# MUTE-basic.net
KiCad netlist of a schematic drawn in EAGLE
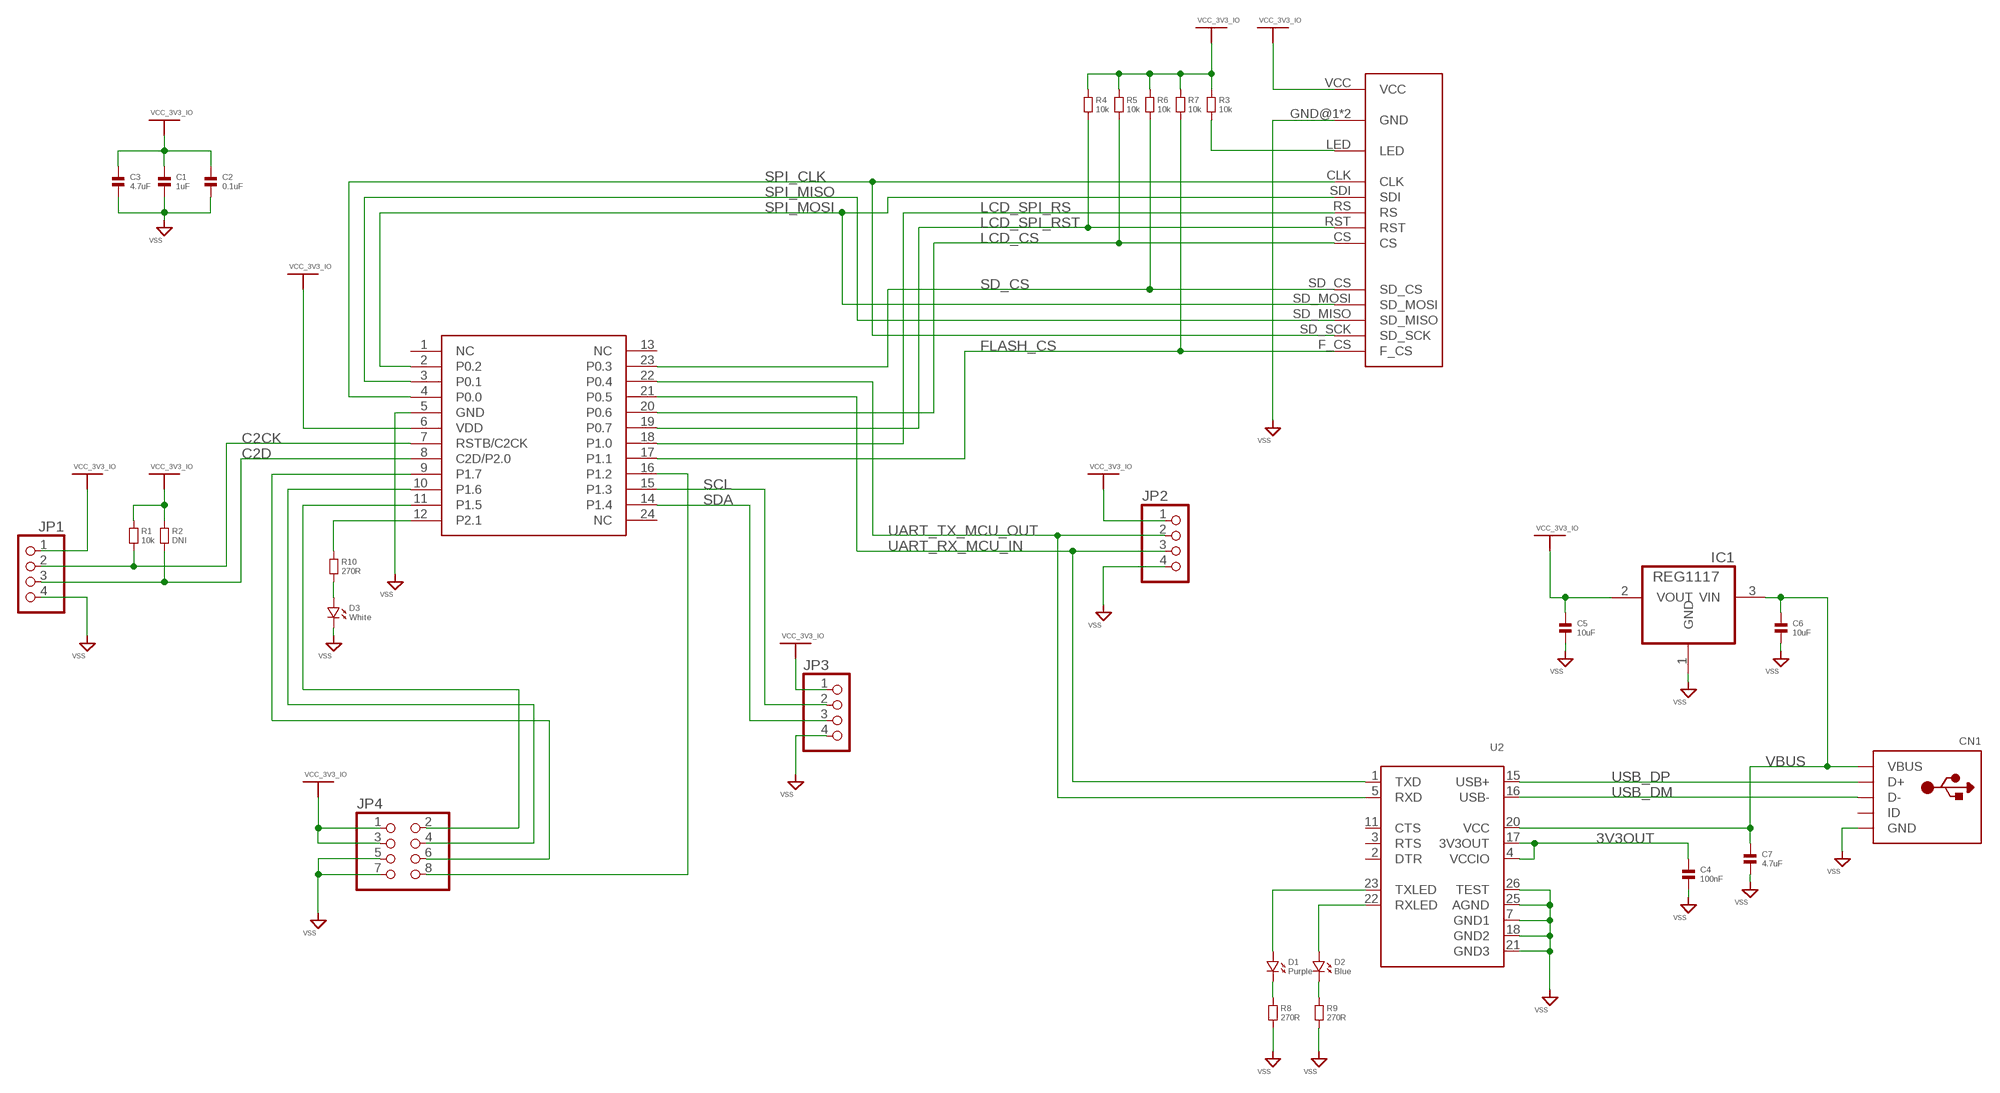
[diagram p0: schematic, sheet 1]

(export (version "E")
  (design (tool "Eeschema 10.0.6"))
  (components
    (comp (ref "C1")
      (value "1uF")
      (footprint "eagle-import:0603")
      (libsource (lib "eagle-import") (part "CAPACITOR.0603"))
    )
    (comp (ref "C2")
      (value "0.1uF")
      (footprint "eagle-import:0603")
      (libsource (lib "eagle-import") (part "CAPACITOR.0603"))
    )
    (comp (ref "C3")
      (value "4.7uF")
      (footprint "eagle-import:0603")
      (libsource (lib "eagle-import") (part "CAPACITOR.0603"))
    )
    (comp (ref "C4")
      (value "100nF")
      (footprint "eagle-import:0603")
      (libsource (lib "eagle-import") (part "CAPACITOR.0603"))
    )
    (comp (ref "C5")
      (value "10uF")
      (footprint "eagle-import:0603")
      (libsource (lib "eagle-import") (part "CAPACITOR.0603"))
    )
    (comp (ref "C6")
      (value "10uF")
      (footprint "eagle-import:0603")
      (libsource (lib "eagle-import") (part "CAPACITOR.0603"))
    )
    (comp (ref "C7")
      (value "4.7uF")
      (footprint "eagle-import:0603")
      (libsource (lib "eagle-import") (part "CAPACITOR.0603"))
    )
    (comp (ref "CN1")
      (value "USBMINIB")
      (footprint "eagle-import:USB-MINIB")
      (libsource (lib "eagle-import") (part "USBMINIB"))
    )
    (comp (ref "D1")
      (value "Purple")
      (footprint "eagle-import:0603.LED")
      (libsource (lib "eagle-import") (part "LED.0603"))
    )
    (comp (ref "D2")
      (value "Blue")
      (footprint "eagle-import:0603.LED")
      (libsource (lib "eagle-import") (part "LED.0603"))
    )
    (comp (ref "D3")
      (value "White")
      (footprint "eagle-import:0603.LED")
      (libsource (lib "eagle-import") (part "LED.0603"))
    )
    (comp (ref "IC1")
      (value "REG1117")
      (footprint "eagle-import:SOT223")
      (libsource (lib "eagle-import") (part "REG1117"))
    )
    (comp (ref "JP1")
      (value "PINHD-1X4")
      (footprint "eagle-import:1X04")
      (libsource (lib "eagle-import") (part "PINHD-1X4"))
    )
    (comp (ref "JP2")
      (value "PINHD-1X4")
      (footprint "eagle-import:1X04")
      (libsource (lib "eagle-import") (part "PINHD-1X4"))
    )
    (comp (ref "JP3")
      (value "PINHD-1X4")
      (footprint "eagle-import:1X04")
      (libsource (lib "eagle-import") (part "PINHD-1X4"))
    )
    (comp (ref "JP4")
      (value "PINHD-2X4")
      (footprint "eagle-import:2X04")
      (libsource (lib "eagle-import") (part "PINHD-2X4"))
    )
    (comp (ref "R1")
      (value "10k")
      (footprint "eagle-import:0603")
      (libsource (lib "eagle-import") (part "RESISTOR.0603"))
    )
    (comp (ref "R2")
      (value "DNI")
      (footprint "eagle-import:0603")
      (libsource (lib "eagle-import") (part "RESISTOR.0603"))
    )
    (comp (ref "R3")
      (value "10k")
      (footprint "eagle-import:0603")
      (libsource (lib "eagle-import") (part "RESISTOR.0603"))
    )
    (comp (ref "R4")
      (value "10k")
      (footprint "eagle-import:0603")
      (libsource (lib "eagle-import") (part "RESISTOR.0603"))
    )
    (comp (ref "R5")
      (value "10k")
      (footprint "eagle-import:0603")
      (libsource (lib "eagle-import") (part "RESISTOR.0603"))
    )
    (comp (ref "R6")
      (value "10k")
      (footprint "eagle-import:0603")
      (libsource (lib "eagle-import") (part "RESISTOR.0603"))
    )
    (comp (ref "R7")
      (value "10k")
      (footprint "eagle-import:0603")
      (libsource (lib "eagle-import") (part "RESISTOR.0603"))
    )
    (comp (ref "R8")
      (value "270R")
      (footprint "eagle-import:0603")
      (libsource (lib "eagle-import") (part "RESISTOR.0603"))
    )
    (comp (ref "R9")
      (value "270R")
      (footprint "eagle-import:0603")
      (libsource (lib "eagle-import") (part "RESISTOR.0603"))
    )
    (comp (ref "R10")
      (value "270R")
      (footprint "eagle-import:0603")
      (libsource (lib "eagle-import") (part "RESISTOR.0603"))
    )
    (comp (ref "U$1")
      (value "WINGONEER_ILI9225")
      (footprint "eagle-import:WINGONEER_ILI9225")
      (libsource (lib "eagle-import") (part "WINGONEER_ILI9225"))
    )
    (comp (ref "U1")
      (value "SILICON_LABS-MICROCONTROLLER-EFM8BB1X")
      (footprint "eagle-import:SILICON_LABS-MICROCONTROLLER-EFM8BB10F8G-A-QSOP24R")
      (libsource (lib "eagle-import") (part "SILICON_LABS-MICROCONTROLLER-EFM8BB1X"))
    )
    (comp (ref "U2")
      (value "FT232RLSSOP28")
      (footprint "eagle-import:SSOP28DB")
      (libsource (lib "eagle-import") (part "FT232RLSSOP28"))
    )
  )
  (nets
    (net (code "1") (name "/3V3OUT") (class "Default")
      (node (ref "C4") (pin "1") (pinfunction "1_1") (pintype "bidirectional"))
      (node (ref "U2") (pin "17") (pinfunction "3V3OUT_17") (pintype "power_in"))
      (node (ref "U2") (pin "4") (pinfunction "VCCIO_4") (pintype "power_in"))
    )
    (net (code "2") (name "/C2CK") (class "Default")
      (node (ref "JP1") (pin "2") (pinfunction "2_2") (pintype "passive"))
      (node (ref "R1") (pin "2") (pinfunction "2_2") (pintype "bidirectional"))
      (node (ref "U1") (pin "7") (pinfunction "RSTB/C2CK_7") (pintype "bidirectional"))
    )
    (net (code "3") (name "/C2D") (class "Default")
      (node (ref "JP1") (pin "3") (pinfunction "3_3") (pintype "passive"))
      (node (ref "R2") (pin "2") (pinfunction "2_2") (pintype "bidirectional"))
      (node (ref "U1") (pin "8") (pinfunction "C2D/P2.0_8") (pintype "bidirectional"))
    )
    (net (code "4") (name "/FLASH_CS") (class "Default")
      (node (ref "R7") (pin "2") (pinfunction "2_2") (pintype "bidirectional"))
      (node (ref "U$1") (pin "F_CS") (pinfunction "F_CS_F_CS") (pintype "bidirectional"))
      (node (ref "U1") (pin "17") (pinfunction "P1.1_17") (pintype "bidirectional"))
    )
    (net (code "5") (name "/LCD_CS") (class "Default")
      (node (ref "R5") (pin "2") (pinfunction "2_2") (pintype "bidirectional"))
      (node (ref "U$1") (pin "CS") (pinfunction "CS_CS") (pintype "bidirectional"))
      (node (ref "U1") (pin "20") (pinfunction "P0.6_20") (pintype "bidirectional"))
    )
    (net (code "6") (name "/LCD_SPI_RS") (class "Default")
      (node (ref "U$1") (pin "RS") (pinfunction "RS_RS") (pintype "bidirectional"))
      (node (ref "U1") (pin "18") (pinfunction "P1.0_18") (pintype "bidirectional"))
    )
    (net (code "7") (name "/LCD_SPI_RST") (class "Default")
      (node (ref "R4") (pin "2") (pinfunction "2_2") (pintype "bidirectional"))
      (node (ref "U$1") (pin "RST") (pinfunction "RST_RST") (pintype "bidirectional"))
      (node (ref "U1") (pin "19") (pinfunction "P0.7_19") (pintype "bidirectional"))
    )
    (net (code "8") (name "/SCL") (class "Default")
      (node (ref "JP3") (pin "2") (pinfunction "2_2") (pintype "passive"))
      (node (ref "U1") (pin "15") (pinfunction "P1.3_15") (pintype "bidirectional"))
    )
    (net (code "9") (name "/SDA") (class "Default")
      (node (ref "JP3") (pin "3") (pinfunction "3_3") (pintype "passive"))
      (node (ref "U1") (pin "14") (pinfunction "P1.4_14") (pintype "bidirectional"))
    )
    (net (code "10") (name "/SD_CS") (class "Default")
      (node (ref "R6") (pin "2") (pinfunction "2_2") (pintype "bidirectional"))
      (node (ref "U$1") (pin "SD_CS") (pinfunction "SD_CS_SD_CS") (pintype "bidirectional"))
      (node (ref "U1") (pin "23") (pinfunction "P0.3_23") (pintype "bidirectional"))
    )
    (net (code "11") (name "/SPI_CLK") (class "Default")
      (node (ref "U$1") (pin "CLK") (pinfunction "CLK_CLK") (pintype "bidirectional"))
      (node (ref "U$1") (pin "SD_SCK") (pinfunction "SD_SCK_SD_SCK") (pintype "bidirectional"))
      (node (ref "U1") (pin "4") (pinfunction "P0.0_4") (pintype "bidirectional"))
    )
    (net (code "12") (name "/SPI_MISO") (class "Default")
      (node (ref "U$1") (pin "SD_MISO") (pinfunction "SD_MISO_SD_MISO") (pintype "bidirectional"))
      (node (ref "U1") (pin "3") (pinfunction "P0.1_3") (pintype "bidirectional"))
    )
    (net (code "13") (name "/SPI_MOSI") (class "Default")
      (node (ref "U$1") (pin "SDI") (pinfunction "SDI_SDI") (pintype "bidirectional"))
      (node (ref "U$1") (pin "SD_MOSI") (pinfunction "SD_MOSI_SD_MOSI") (pintype "bidirectional"))
      (node (ref "U1") (pin "2") (pinfunction "P0.2_2") (pintype "bidirectional"))
    )
    (net (code "14") (name "/UART_RX_MCU_IN") (class "Default")
      (node (ref "JP2") (pin "3") (pinfunction "3_3") (pintype "passive"))
      (node (ref "U1") (pin "21") (pinfunction "P0.5_21") (pintype "bidirectional"))
      (node (ref "U2") (pin "1") (pinfunction "TXD_1") (pintype "output"))
    )
    (net (code "15") (name "/UART_TX_MCU_OUT") (class "Default")
      (node (ref "JP2") (pin "2") (pinfunction "2_2") (pintype "passive"))
      (node (ref "U1") (pin "22") (pinfunction "P0.4_22") (pintype "bidirectional"))
      (node (ref "U2") (pin "5") (pinfunction "RXD_5") (pintype "input"))
    )
    (net (code "16") (name "/USB_DM") (class "Default")
      (node (ref "CN1") (pin "D-") (pinfunction "D-_D-") (pintype "bidirectional"))
      (node (ref "U2") (pin "16") (pinfunction "USB-_16") (pintype "bidirectional"))
    )
    (net (code "17") (name "/USB_DP") (class "Default")
      (node (ref "CN1") (pin "D+") (pinfunction "D+_D+") (pintype "bidirectional"))
      (node (ref "U2") (pin "15") (pinfunction "USB+_15") (pintype "bidirectional"))
    )
    (net (code "18") (name "/VBUS") (class "Default")
      (node (ref "C6") (pin "1") (pinfunction "1_1") (pintype "bidirectional"))
      (node (ref "C7") (pin "1") (pinfunction "1_1") (pintype "bidirectional"))
      (node (ref "CN1") (pin "VBUS") (pinfunction "VBUS_VBUS") (pintype "power_in"))
      (node (ref "IC1") (pin "3") (pinfunction "VIN_3") (pintype "input"))
      (node (ref "U2") (pin "20") (pinfunction "VCC_20") (pintype "power_in"))
    )
    (net (code "19") (name "Net-(D1-1)") (class "Default")
      (node (ref "D1") (pin "P$1") (pinfunction "1_P$1") (pintype "bidirectional"))
      (node (ref "U2") (pin "23") (pinfunction "TXLED_23") (pintype "bidirectional"))
    )
    (net (code "20") (name "Net-(D1-2)") (class "Default")
      (node (ref "D1") (pin "P$2") (pinfunction "2_P$2") (pintype "bidirectional"))
      (node (ref "R8") (pin "1") (pinfunction "1_1") (pintype "bidirectional"))
    )
    (net (code "21") (name "Net-(D2-1)") (class "Default")
      (node (ref "D2") (pin "P$1") (pinfunction "1_P$1") (pintype "bidirectional"))
      (node (ref "U2") (pin "22") (pinfunction "RXLED_22") (pintype "bidirectional"))
    )
    (net (code "22") (name "Net-(D2-2)") (class "Default")
      (node (ref "D2") (pin "P$2") (pinfunction "2_P$2") (pintype "bidirectional"))
      (node (ref "R9") (pin "1") (pinfunction "1_1") (pintype "bidirectional"))
    )
    (net (code "23") (name "Net-(D3-1)") (class "Default")
      (node (ref "D3") (pin "P$1") (pinfunction "1_P$1") (pintype "bidirectional"))
      (node (ref "R10") (pin "2") (pinfunction "2_2") (pintype "bidirectional"))
    )
    (net (code "24") (name "Net-(R3-Pad2)") (class "Default")
      (node (ref "R3") (pin "2") (pinfunction "2_2") (pintype "bidirectional"))
      (node (ref "U$1") (pin "LED") (pinfunction "LED_LED") (pintype "bidirectional"))
    )
    (net (code "25") (name "Net-(U1-P1.2)") (class "Default")
      (node (ref "JP4") (pin "8") (pinfunction "8_8") (pintype "passive"))
      (node (ref "U1") (pin "16") (pinfunction "P1.2_16") (pintype "bidirectional"))
    )
    (net (code "26") (name "Net-(U1-P1.5)") (class "Default")
      (node (ref "JP4") (pin "2") (pinfunction "2_2") (pintype "passive"))
      (node (ref "U1") (pin "11") (pinfunction "P1.5_11") (pintype "bidirectional"))
    )
    (net (code "27") (name "Net-(U1-P1.6)") (class "Default")
      (node (ref "JP4") (pin "4") (pinfunction "4_4") (pintype "passive"))
      (node (ref "U1") (pin "10") (pinfunction "P1.6_10") (pintype "bidirectional"))
    )
    (net (code "28") (name "Net-(U1-P1.7)") (class "Default")
      (node (ref "JP4") (pin "6") (pinfunction "6_6") (pintype "passive"))
      (node (ref "U1") (pin "9") (pinfunction "P1.7_9") (pintype "bidirectional"))
    )
    (net (code "29") (name "Net-(U1-P2.1)") (class "Default")
      (node (ref "R10") (pin "1") (pinfunction "1_1") (pintype "bidirectional"))
      (node (ref "U1") (pin "12") (pinfunction "P2.1_12") (pintype "bidirectional"))
    )
    (net (code "30") (name "VCC_3V3_IO") (class "Default")
      (node (ref "C1") (pin "1") (pinfunction "1_1") (pintype "bidirectional"))
      (node (ref "C2") (pin "1") (pinfunction "1_1") (pintype "bidirectional"))
      (node (ref "C3") (pin "1") (pinfunction "1_1") (pintype "bidirectional"))
      (node (ref "C5") (pin "1") (pinfunction "1_1") (pintype "bidirectional"))
      (node (ref "IC1") (pin "2") (pinfunction "VOUT_2") (pintype "output"))
      (node (ref "JP1") (pin "1") (pinfunction "1_1") (pintype "passive"))
      (node (ref "JP2") (pin "1") (pinfunction "1_1") (pintype "passive"))
      (node (ref "JP3") (pin "1") (pinfunction "1_1") (pintype "passive"))
      (node (ref "JP4") (pin "1") (pinfunction "1_1") (pintype "passive"))
      (node (ref "JP4") (pin "3") (pinfunction "3_3") (pintype "passive"))
      (node (ref "R1") (pin "1") (pinfunction "1_1") (pintype "bidirectional"))
      (node (ref "R2") (pin "1") (pinfunction "1_1") (pintype "bidirectional"))
      (node (ref "R3") (pin "1") (pinfunction "1_1") (pintype "bidirectional"))
      (node (ref "R4") (pin "1") (pinfunction "1_1") (pintype "bidirectional"))
      (node (ref "R5") (pin "1") (pinfunction "1_1") (pintype "bidirectional"))
      (node (ref "R6") (pin "1") (pinfunction "1_1") (pintype "bidirectional"))
      (node (ref "R7") (pin "1") (pinfunction "1_1") (pintype "bidirectional"))
      (node (ref "U$1") (pin "VCC") (pinfunction "VCC_VCC") (pintype "bidirectional"))
      (node (ref "U1") (pin "6") (pinfunction "VDD_6") (pintype "bidirectional"))
    )
    (net (code "31") (name "VSS") (class "Default")
      (node (ref "C1") (pin "2") (pinfunction "2_2") (pintype "bidirectional"))
      (node (ref "C2") (pin "2") (pinfunction "2_2") (pintype "bidirectional"))
      (node (ref "C3") (pin "2") (pinfunction "2_2") (pintype "bidirectional"))
      (node (ref "C4") (pin "2") (pinfunction "2_2") (pintype "bidirectional"))
      (node (ref "C5") (pin "2") (pinfunction "2_2") (pintype "bidirectional"))
      (node (ref "C6") (pin "2") (pinfunction "2_2") (pintype "bidirectional"))
      (node (ref "C7") (pin "2") (pinfunction "2_2") (pintype "bidirectional"))
      (node (ref "CN1") (pin "GND") (pinfunction "GND_GND") (pintype "power_in"))
      (node (ref "D3") (pin "P$2") (pinfunction "2_P$2") (pintype "bidirectional"))
      (node (ref "IC1") (pin "1") (pinfunction "GND_1") (pintype "power_in"))
      (node (ref "JP1") (pin "4") (pinfunction "4_4") (pintype "passive"))
      (node (ref "JP2") (pin "4") (pinfunction "4_4") (pintype "passive"))
      (node (ref "JP3") (pin "4") (pinfunction "4_4") (pintype "passive"))
      (node (ref "JP4") (pin "5") (pinfunction "5_5") (pintype "passive"))
      (node (ref "JP4") (pin "7") (pinfunction "7_7") (pintype "passive"))
      (node (ref "R8") (pin "2") (pinfunction "2_2") (pintype "bidirectional"))
      (node (ref "R9") (pin "2") (pinfunction "2_2") (pintype "bidirectional"))
      (node (ref "U$1") (pin "GND@1") (pinfunction "GND_GND@1") (pintype "bidirectional"))
      (node (ref "U$1") (pin "GND@2") (pinfunction "GND_GND@2") (pintype "bidirectional"))
      (node (ref "U1") (pin "5") (pinfunction "GND_5") (pintype "bidirectional"))
      (node (ref "U2") (pin "18") (pinfunction "GND2_18") (pintype "power_in"))
      (node (ref "U2") (pin "21") (pinfunction "GND3_21") (pintype "power_in"))
      (node (ref "U2") (pin "25") (pinfunction "AGND_25") (pintype "power_in"))
      (node (ref "U2") (pin "26") (pinfunction "TEST_26") (pintype "input"))
      (node (ref "U2") (pin "7") (pinfunction "GND1_7") (pintype "power_in"))
    )
    (net (code "32") (name "unconnected-(CN1-PadID)") (class "Default")
      (node (ref "CN1") (pin "ID") (pinfunction "ID_ID") (pintype "bidirectional"))
    )
    (net (code "33") (name "unconnected-(U1-NC-Pad1)") (class "Default")
      (node (ref "U1") (pin "1") (pinfunction "NC_1") (pintype "bidirectional"))
    )
    (net (code "34") (name "unconnected-(U1-NC-Pad13)") (class "Default")
      (node (ref "U1") (pin "13") (pinfunction "NC_13") (pintype "bidirectional"))
    )
    (net (code "35") (name "unconnected-(U1-NC-Pad24)") (class "Default")
      (node (ref "U1") (pin "24") (pinfunction "NC_24") (pintype "bidirectional"))
    )
    (net (code "36") (name "unconnected-(U2-CTS-Pad11)") (class "Default")
      (node (ref "U2") (pin "11") (pinfunction "CTS_11") (pintype "bidirectional"))
    )
    (net (code "37") (name "unconnected-(U2-DTR-Pad2)") (class "Default")
      (node (ref "U2") (pin "2") (pinfunction "DTR_2") (pintype "bidirectional"))
    )
    (net (code "38") (name "unconnected-(U2-RTS-Pad3)") (class "Default")
      (node (ref "U2") (pin "3") (pinfunction "RTS_3") (pintype "bidirectional"))
    )
  )
)
